# PSUs.net
KiCad netlist of a schematic drawn in Altium Designer
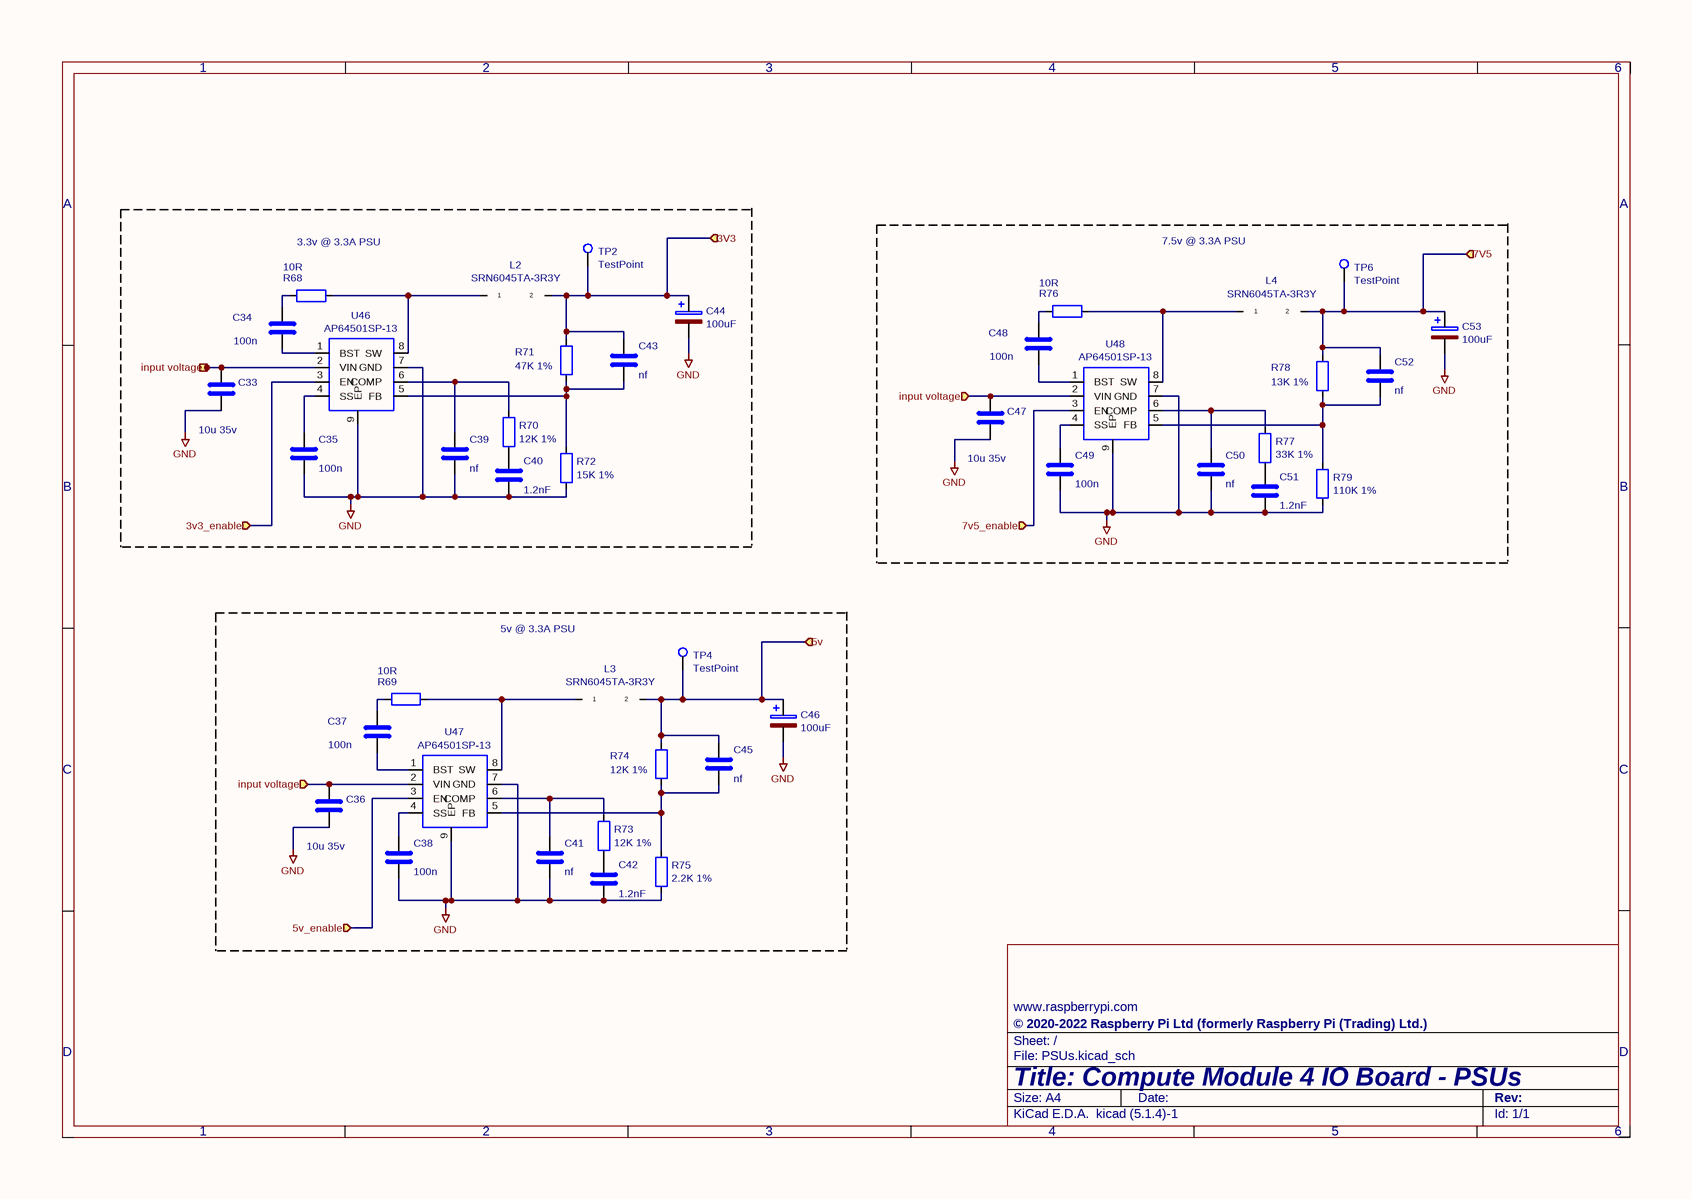
[diagram p0: PSUs.SchDoc]

(export (version "E")
  (design (tool "Eeschema 10.0.6"))
  (components
    (comp (ref "C33") (value "10u 35v") (footprint "C_0805_2012Metric") (libsource (lib "Device") (part "C")))
    (comp (ref "C34") (value "100n") (footprint "C_0805_2012Metric") (libsource (lib "Device") (part "C")))
    (comp (ref "C35") (value "100n") (footprint "C_0805_2012Metric") (libsource (lib "Device") (part "C")))
    (comp (ref "C36") (value "10u 35v") (footprint "C_0805_2012Metric") (libsource (lib "Device") (part "C")))
    (comp (ref "C37") (value "100n") (footprint "C_0805_2012Metric") (libsource (lib "Device") (part "C")))
    (comp (ref "C38") (value "100n") (footprint "C_0805_2012Metric") (libsource (lib "Device") (part "C")))
    (comp (ref "C39") (value "nf") (footprint "C_0805_2012Metric") (libsource (lib "Device") (part "C")))
    (comp (ref "C40") (value "1.2nF") (footprint "C_0805_2012Metric") (libsource (lib "Device") (part "C")))
    (comp (ref "C41") (value "nf") (footprint "C_0805_2012Metric") (libsource (lib "Device") (part "C")))
    (comp (ref "C42") (value "1.2nF") (footprint "C_0805_2012Metric") (libsource (lib "Device") (part "C")))
    (comp (ref "C43") (value "nf") (footprint "C_0805_2012Metric") (libsource (lib "Device") (part "C")))
    (comp (ref "C44")
      (value "100uF")
      (footprint "CP_EIA-7343-31_Kemet-D")
      (libsource (lib "Device") (part "CP"))
    )
    (comp (ref "C45") (value "nf") (footprint "C_0805_2012Metric") (libsource (lib "Device") (part "C")))
    (comp (ref "C46")
      (value "100uF")
      (footprint "CP_EIA-7343-31_Kemet-D")
      (libsource (lib "Device") (part "CP"))
    )
    (comp (ref "C47") (value "10u 35v") (footprint "C_0805_2012Metric") (libsource (lib "Device") (part "C")))
    (comp (ref "C48") (value "100n") (footprint "C_0805_2012Metric") (libsource (lib "Device") (part "C")))
    (comp (ref "C49") (value "100n") (footprint "C_0805_2012Metric") (libsource (lib "Device") (part "C")))
    (comp (ref "C50") (value "nf") (footprint "C_0805_2012Metric") (libsource (lib "Device") (part "C")))
    (comp (ref "C51") (value "1.2nF") (footprint "C_0805_2012Metric") (libsource (lib "Device") (part "C")))
    (comp (ref "C52") (value "nf") (footprint "C_0805_2012Metric") (libsource (lib "Device") (part "C")))
    (comp (ref "C53")
      (value "100uF")
      (footprint "CP_EIA-7343-31_Kemet-D")
      (libsource (lib "Device") (part "CP"))
    )
    (comp (ref "L2")
      (value "SRN6045TA-3R3Y")
      (footprint "L_Bourns_SRN6045TA")
      (libsource (lib "pspice") (part "INDUCTOR"))
    )
    (comp (ref "L3")
      (value "SRN6045TA-3R3Y")
      (footprint "L_Bourns_SRN6045TA")
      (libsource (lib "pspice") (part "INDUCTOR"))
    )
    (comp (ref "L4")
      (value "SRN6045TA-3R3Y")
      (footprint "L_Bourns_SRN6045TA")
      (libsource (lib "pspice") (part "INDUCTOR"))
    )
    (comp (ref "R68")
      (value "10R")
      (footprint "R_0805_2012Metric_Pad1.20x1.40mm_HandSolder")
      (libsource (lib "Device") (part "R"))
    )
    (comp (ref "R69")
      (value "10R")
      (footprint "R_0805_2012Metric_Pad1.20x1.40mm_HandSolder")
      (libsource (lib "Device") (part "R"))
    )
    (comp (ref "R70")
      (value "12K 1%")
      (footprint "R_0805_2012Metric_Pad1.20x1.40mm_HandSolder")
      (libsource (lib "") (part "R_1"))
    )
    (comp (ref "R71")
      (value "47K 1%")
      (footprint "R_0805_2012Metric_Pad1.20x1.40mm_HandSolder")
      (libsource (lib "") (part "R_1"))
    )
    (comp (ref "R72")
      (value "15K 1%")
      (footprint "R_0805_2012Metric_Pad1.20x1.40mm_HandSolder")
      (libsource (lib "") (part "R_1"))
    )
    (comp (ref "R73")
      (value "12K 1%")
      (footprint "R_0805_2012Metric_Pad1.20x1.40mm_HandSolder")
      (libsource (lib "") (part "R_1"))
    )
    (comp (ref "R74")
      (value "12K 1%")
      (footprint "R_0805_2012Metric_Pad1.20x1.40mm_HandSolder")
      (libsource (lib "") (part "R_1"))
    )
    (comp (ref "R75")
      (value "2.2K 1%")
      (footprint "R_0805_2012Metric_Pad1.20x1.40mm_HandSolder")
      (libsource (lib "") (part "R_1"))
    )
    (comp (ref "R76")
      (value "10R")
      (footprint "R_0805_2012Metric_Pad1.20x1.40mm_HandSolder")
      (libsource (lib "Device") (part "R"))
    )
    (comp (ref "R77")
      (value "33K 1%")
      (footprint "R_0805_2012Metric_Pad1.20x1.40mm_HandSolder")
      (libsource (lib "") (part "R_1"))
    )
    (comp (ref "R78")
      (value "13K 1%")
      (footprint "R_0805_2012Metric_Pad1.20x1.40mm_HandSolder")
      (libsource (lib "") (part "R_1"))
    )
    (comp (ref "R79")
      (value "110K 1%")
      (footprint "R_0805_2012Metric_Pad1.20x1.40mm_HandSolder")
      (libsource (lib "") (part "R_1"))
    )
    (comp (ref "TP2")
      (value "TestPoint")
      (footprint "TestPoint_Pad_1.0x1.0mm")
      (libsource (lib "Connector") (part "TestPoint"))
    )
    (comp (ref "TP4")
      (value "TestPoint")
      (footprint "TestPoint_Pad_1.0x1.0mm")
      (libsource (lib "Connector") (part "TestPoint"))
    )
    (comp (ref "TP6")
      (value "TestPoint")
      (footprint "TestPoint_Pad_1.0x1.0mm")
      (libsource (lib "Connector") (part "TestPoint"))
    )
    (comp (ref "U46")
      (value "AP64501SP-13")
      (footprint "SOIC-8-1EP_3.9x4.9mm_P1.27mm_EP2.95x4.9mm_Mask2.71x3.4mm_ThermalVias")
      (libsource (lib "CM4IO") (part "AP64351"))
    )
    (comp (ref "U47")
      (value "AP64501SP-13")
      (footprint "SOIC-8-1EP_3.9x4.9mm_P1.27mm_EP2.95x4.9mm_Mask2.71x3.4mm_ThermalVias")
      (libsource (lib "CM4IO") (part "AP64351"))
    )
    (comp (ref "U48")
      (value "AP64501SP-13")
      (footprint "SOIC-8-1EP_3.9x4.9mm_P1.27mm_EP2.95x4.9mm_Mask2.71x3.4mm_ThermalVias")
      (libsource (lib "CM4IO") (part "AP64351"))
    )
  )
  (nets
    (net (code "1") (name "/3V3") (class "Default")
      (node (ref "C43") (pin "1") (pinfunction "1_1") (pintype "passive"))
      (node (ref "C44") (pin "1") (pinfunction "1_1") (pintype "passive"))
      (node (ref "L2") (pin "2") (pinfunction "2_2") (pintype "passive"))
      (node (ref "R71") (pin "1") (pinfunction "1_1") (pintype "passive"))
      (node (ref "TP2") (pin "1") (pinfunction "1_1") (pintype "passive"))
    )
    (net (code "2") (name "/3v3_enable") (class "Default")
      (node (ref "U46") (pin "3") (pinfunction "EN_3") (pintype "passive"))
    )
    (net (code "3") (name "/5v") (class "Default")
      (node (ref "C45") (pin "1") (pinfunction "1_1") (pintype "passive"))
      (node (ref "C46") (pin "1") (pinfunction "1_1") (pintype "passive"))
      (node (ref "L3") (pin "2") (pinfunction "2_2") (pintype "passive"))
      (node (ref "R74") (pin "1") (pinfunction "1_1") (pintype "passive"))
      (node (ref "TP4") (pin "1") (pinfunction "1_1") (pintype "passive"))
    )
    (net (code "4") (name "/5v_enable") (class "Default")
      (node (ref "U47") (pin "3") (pinfunction "EN_3") (pintype "passive"))
    )
    (net (code "5") (name "/7V5") (class "Default")
      (node (ref "C52") (pin "1") (pinfunction "1_1") (pintype "passive"))
      (node (ref "C53") (pin "1") (pinfunction "1_1") (pintype "passive"))
      (node (ref "L4") (pin "2") (pinfunction "2_2") (pintype "passive"))
      (node (ref "R78") (pin "1") (pinfunction "1_1") (pintype "passive"))
      (node (ref "TP6") (pin "1") (pinfunction "1_1") (pintype "passive"))
    )
    (net (code "6") (name "/7v5_enable") (class "Default")
      (node (ref "U48") (pin "3") (pinfunction "EN_3") (pintype "passive"))
    )
    (net (code "7") (name "/input voltage") (class "Default")
      (node (ref "C33") (pin "1") (pinfunction "1_1") (pintype "passive"))
      (node (ref "C36") (pin "1") (pinfunction "1_1") (pintype "passive"))
      (node (ref "C47") (pin "1") (pinfunction "1_1") (pintype "passive"))
      (node (ref "U46") (pin "2") (pinfunction "VIN_2") (pintype "passive"))
      (node (ref "U47") (pin "2") (pinfunction "VIN_2") (pintype "passive"))
      (node (ref "U48") (pin "2") (pinfunction "VIN_2") (pintype "passive"))
    )
    (net (code "8") (name "GND") (class "Default")
      (node (ref "C33") (pin "2") (pinfunction "2_2") (pintype "passive"))
      (node (ref "C35") (pin "2") (pinfunction "2_2") (pintype "passive"))
      (node (ref "C36") (pin "2") (pinfunction "2_2") (pintype "passive"))
      (node (ref "C38") (pin "2") (pinfunction "2_2") (pintype "passive"))
      (node (ref "C39") (pin "2") (pinfunction "2_2") (pintype "passive"))
      (node (ref "C40") (pin "2") (pinfunction "2_2") (pintype "passive"))
      (node (ref "C41") (pin "2") (pinfunction "2_2") (pintype "passive"))
      (node (ref "C42") (pin "2") (pinfunction "2_2") (pintype "passive"))
      (node (ref "C44") (pin "2") (pinfunction "2_2") (pintype "passive"))
      (node (ref "C46") (pin "2") (pinfunction "2_2") (pintype "passive"))
      (node (ref "C47") (pin "2") (pinfunction "2_2") (pintype "passive"))
      (node (ref "C49") (pin "2") (pinfunction "2_2") (pintype "passive"))
      (node (ref "C50") (pin "2") (pinfunction "2_2") (pintype "passive"))
      (node (ref "C51") (pin "2") (pinfunction "2_2") (pintype "passive"))
      (node (ref "C53") (pin "2") (pinfunction "2_2") (pintype "passive"))
      (node (ref "R72") (pin "2") (pinfunction "2_2") (pintype "passive"))
      (node (ref "R75") (pin "2") (pinfunction "2_2") (pintype "passive"))
      (node (ref "R79") (pin "2") (pinfunction "2_2") (pintype "passive"))
      (node (ref "U46") (pin "7") (pinfunction "GND_7") (pintype "passive"))
      (node (ref "U46") (pin "9") (pinfunction "EP_9") (pintype "passive"))
      (node (ref "U47") (pin "7") (pinfunction "GND_7") (pintype "passive"))
      (node (ref "U47") (pin "9") (pinfunction "EP_9") (pintype "passive"))
      (node (ref "U48") (pin "7") (pinfunction "GND_7") (pintype "passive"))
      (node (ref "U48") (pin "9") (pinfunction "EP_9") (pintype "passive"))
    )
    (net (code "9") (name "Net-(C34-Pad1)") (class "Default")
      (node (ref "C34") (pin "1") (pinfunction "1_1") (pintype "passive"))
      (node (ref "R68") (pin "2") (pinfunction "2_2") (pintype "passive"))
    )
    (net (code "10") (name "Net-(C37-Pad1)") (class "Default")
      (node (ref "C37") (pin "1") (pinfunction "1_1") (pintype "passive"))
      (node (ref "R69") (pin "2") (pinfunction "2_2") (pintype "passive"))
    )
    (net (code "11") (name "Net-(C40-Pad1)") (class "Default")
      (node (ref "C40") (pin "1") (pinfunction "1_1") (pintype "passive"))
      (node (ref "R70") (pin "2") (pinfunction "2_2") (pintype "passive"))
    )
    (net (code "12") (name "Net-(C42-Pad1)") (class "Default")
      (node (ref "C42") (pin "1") (pinfunction "1_1") (pintype "passive"))
      (node (ref "R73") (pin "2") (pinfunction "2_2") (pintype "passive"))
    )
    (net (code "13") (name "Net-(C48-Pad1)") (class "Default")
      (node (ref "C48") (pin "1") (pinfunction "1_1") (pintype "passive"))
      (node (ref "R76") (pin "2") (pinfunction "2_2") (pintype "passive"))
    )
    (net (code "14") (name "Net-(C51-Pad1)") (class "Default")
      (node (ref "C51") (pin "1") (pinfunction "1_1") (pintype "passive"))
      (node (ref "R77") (pin "2") (pinfunction "2_2") (pintype "passive"))
    )
    (net (code "15") (name "Net-(U46-BST)") (class "Default")
      (node (ref "C34") (pin "2") (pinfunction "2_2") (pintype "passive"))
      (node (ref "U46") (pin "1") (pinfunction "BST_1") (pintype "passive"))
    )
    (net (code "16") (name "Net-(U46-COMP)") (class "Default")
      (node (ref "C39") (pin "1") (pinfunction "1_1") (pintype "passive"))
      (node (ref "R70") (pin "1") (pinfunction "1_1") (pintype "passive"))
      (node (ref "U46") (pin "6") (pinfunction "COMP_6") (pintype "passive"))
    )
    (net (code "17") (name "Net-(U46-FB)") (class "Default")
      (node (ref "C43") (pin "2") (pinfunction "2_2") (pintype "passive"))
      (node (ref "R71") (pin "2") (pinfunction "2_2") (pintype "passive"))
      (node (ref "R72") (pin "1") (pinfunction "1_1") (pintype "passive"))
      (node (ref "U46") (pin "5") (pinfunction "FB_5") (pintype "passive"))
    )
    (net (code "18") (name "Net-(U46-SS)") (class "Default")
      (node (ref "C35") (pin "1") (pinfunction "1_1") (pintype "passive"))
      (node (ref "U46") (pin "4") (pinfunction "SS_4") (pintype "passive"))
    )
    (net (code "19") (name "Net-(U46-SW)") (class "Default")
      (node (ref "L2") (pin "1") (pinfunction "1_1") (pintype "passive"))
      (node (ref "R68") (pin "1") (pinfunction "1_1") (pintype "passive"))
      (node (ref "U46") (pin "8") (pinfunction "SW_8") (pintype "passive"))
    )
    (net (code "20") (name "Net-(U47-BST)") (class "Default")
      (node (ref "C37") (pin "2") (pinfunction "2_2") (pintype "passive"))
      (node (ref "U47") (pin "1") (pinfunction "BST_1") (pintype "passive"))
    )
    (net (code "21") (name "Net-(U47-COMP)") (class "Default")
      (node (ref "C41") (pin "1") (pinfunction "1_1") (pintype "passive"))
      (node (ref "R73") (pin "1") (pinfunction "1_1") (pintype "passive"))
      (node (ref "U47") (pin "6") (pinfunction "COMP_6") (pintype "passive"))
    )
    (net (code "22") (name "Net-(U47-FB)") (class "Default")
      (node (ref "C45") (pin "2") (pinfunction "2_2") (pintype "passive"))
      (node (ref "R74") (pin "2") (pinfunction "2_2") (pintype "passive"))
      (node (ref "R75") (pin "1") (pinfunction "1_1") (pintype "passive"))
      (node (ref "U47") (pin "5") (pinfunction "FB_5") (pintype "passive"))
    )
    (net (code "23") (name "Net-(U47-SS)") (class "Default")
      (node (ref "C38") (pin "1") (pinfunction "1_1") (pintype "passive"))
      (node (ref "U47") (pin "4") (pinfunction "SS_4") (pintype "passive"))
    )
    (net (code "24") (name "Net-(U47-SW)") (class "Default")
      (node (ref "L3") (pin "1") (pinfunction "1_1") (pintype "passive"))
      (node (ref "R69") (pin "1") (pinfunction "1_1") (pintype "passive"))
      (node (ref "U47") (pin "8") (pinfunction "SW_8") (pintype "passive"))
    )
    (net (code "25") (name "Net-(U48-BST)") (class "Default")
      (node (ref "C48") (pin "2") (pinfunction "2_2") (pintype "passive"))
      (node (ref "U48") (pin "1") (pinfunction "BST_1") (pintype "passive"))
    )
    (net (code "26") (name "Net-(U48-COMP)") (class "Default")
      (node (ref "C50") (pin "1") (pinfunction "1_1") (pintype "passive"))
      (node (ref "R77") (pin "1") (pinfunction "1_1") (pintype "passive"))
      (node (ref "U48") (pin "6") (pinfunction "COMP_6") (pintype "passive"))
    )
    (net (code "27") (name "Net-(U48-FB)") (class "Default")
      (node (ref "C52") (pin "2") (pinfunction "2_2") (pintype "passive"))
      (node (ref "R78") (pin "2") (pinfunction "2_2") (pintype "passive"))
      (node (ref "R79") (pin "1") (pinfunction "1_1") (pintype "passive"))
      (node (ref "U48") (pin "5") (pinfunction "FB_5") (pintype "passive"))
    )
    (net (code "28") (name "Net-(U48-SS)") (class "Default")
      (node (ref "C49") (pin "1") (pinfunction "1_1") (pintype "passive"))
      (node (ref "U48") (pin "4") (pinfunction "SS_4") (pintype "passive"))
    )
    (net (code "29") (name "Net-(U48-SW)") (class "Default")
      (node (ref "L4") (pin "1") (pinfunction "1_1") (pintype "passive"))
      (node (ref "R76") (pin "1") (pinfunction "1_1") (pintype "passive"))
      (node (ref "U48") (pin "8") (pinfunction "SW_8") (pintype "passive"))
    )
  )
)
